# Buck_Converter_and_LDO.net
KiCad netlist of a schematic drawn in Altium Designer
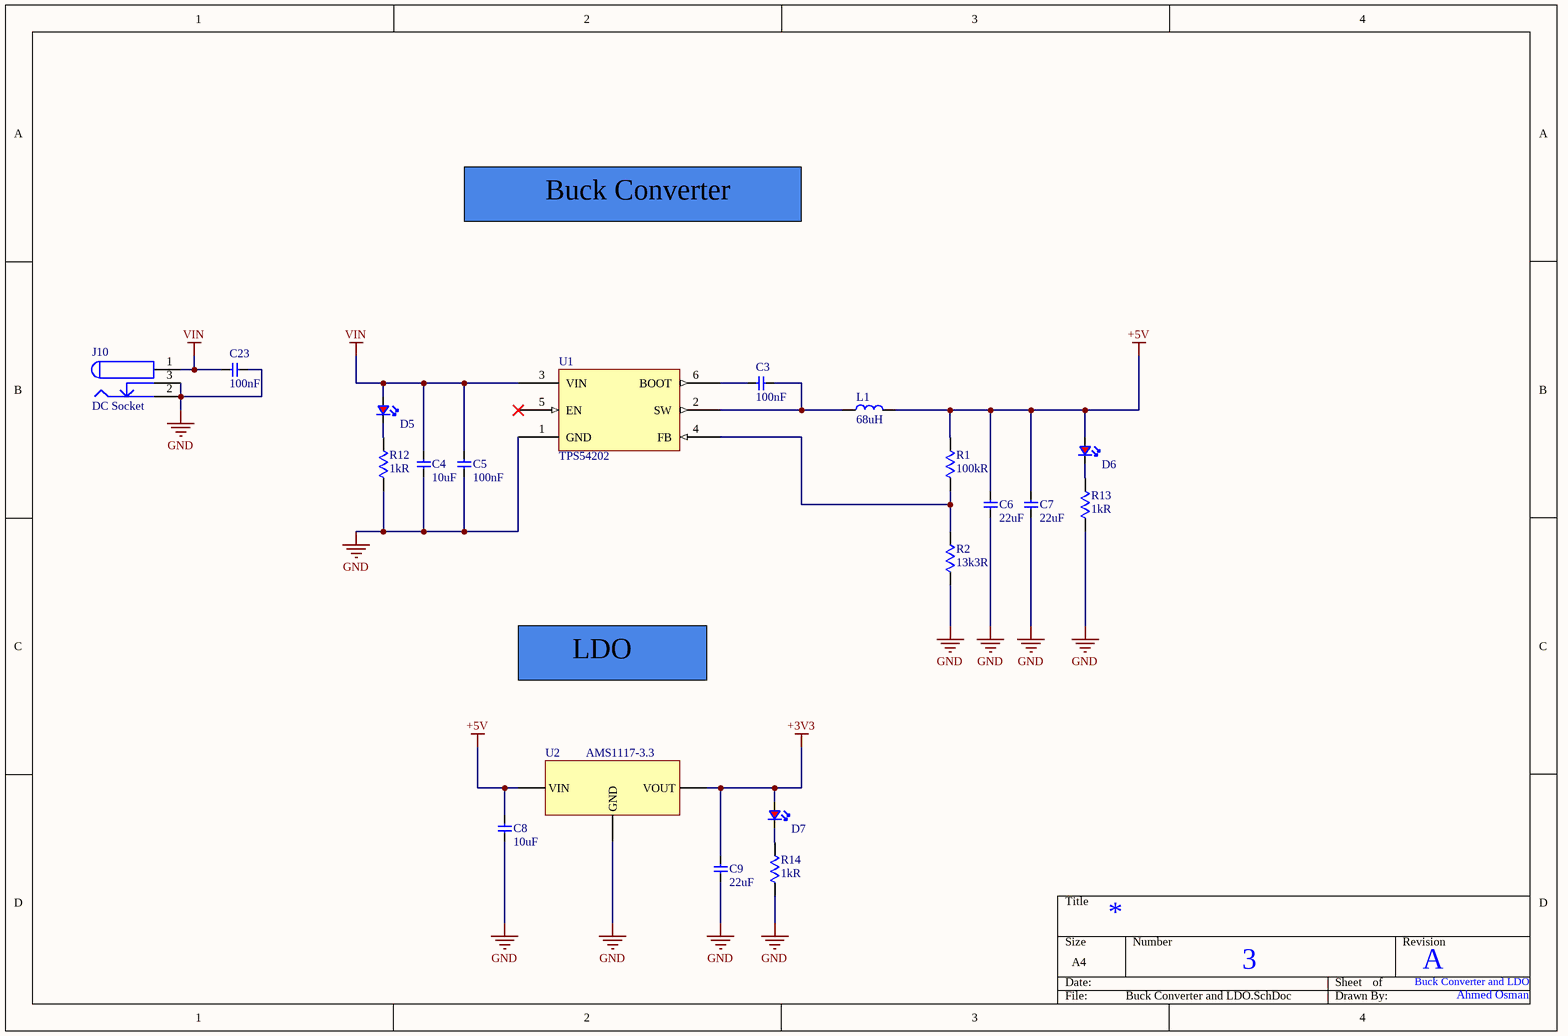
[diagram p0: Buck Converter and LDO.SchDoc]

(export (version "E")
  (design (tool "Eeschema 10.0.6"))
  (components
    (comp (ref "C3")
      (value "100nF")
      (footprint "CAP 0603")
      (description "0.1 µF ±10% 50V Ceramic Capacitor X7R 0603 (1608 Metric)")
      (fields (field (name "TOLERANCE") "10%") (field (name "VOLTAGE") "50V"))
      (libsource (lib "Temperature project symbols") (part "CAP  0603 100nF 10% 50 V"))
    )
    (comp (ref "C4")
      (value "10uF")
      (footprint "CAP 0603")
      (description "10 µF ±20% 35V Ceramic Capacitor X5R 0603 (1608 Metric)")
      (fields
        (field (name "MANUFACTURER") "Murata")
        (field (name "MANUFACTURER PART NUMBER") "GRM188R6YA106MA73D")
      )
      (libsource (lib "Temperature project symbols") (part "CAP 0603 10 µF ±20% 35V _1"))
    )
    (comp (ref "C5")
      (value "100nF")
      (footprint "CAP 0603")
      (description "0.1 µF ±10% 50V Ceramic Capacitor X7R 0603 (1608 Metric)")
      (fields (field (name "TOLERANCE") "10%") (field (name "VOLTAGE") "50V"))
      (libsource (lib "Temperature project symbols") (part "CAP  0603 100nF 10% 50 V"))
    )
    (comp (ref "C6")
      (value "22uF")
      (footprint "CAP 0603")
      (description "10V 22uF X5R ±20% 0603 Multilayer Ceramic Capacitors MLCC - SMD/SMT ROHS")
      (libsource (lib "Temperature project symbols") (part "CAP  0603 22 µF ±20% 10V"))
    )
    (comp (ref "C7")
      (value "22uF")
      (footprint "CAP 0603")
      (description "10V 22uF X5R ±20% 0603 Multilayer Ceramic Capacitors MLCC - SMD/SMT ROHS")
      (libsource (lib "Temperature project symbols") (part "CAP  0603 22 µF ±20% 10V"))
    )
    (comp (ref "C8")
      (value "10uF")
      (footprint "CAP 0603")
      (description "10 µF ±20% 35V Ceramic Capacitor X5R 0603 (1608 Metric)")
      (fields
        (field (name "MANUFACTURER") "Murata")
        (field (name "MANUFACTURER PART NUMBER") "GRM188R6YA106MA73D")
      )
      (libsource (lib "Temperature project symbols") (part "CAP 0603 10 µF ±20% 35V"))
    )
    (comp (ref "C9")
      (value "22uF")
      (footprint "CAP 0603")
      (description "10V 22uF X5R ±20% 0603 Multilayer Ceramic Capacitors MLCC - SMD/SMT ROHS")
      (libsource (lib "Temperature project symbols") (part "CAP  0603 22 µF ±20% 10V"))
    )
    (comp (ref "C23")
      (value "100nF")
      (footprint "CAP 0603")
      (description "0.1 µF ±10% 50V Ceramic Capacitor X7R 0603 (1608 Metric)")
      (fields (field (name "TOLERANCE") "10%") (field (name "VOLTAGE") "50V"))
      (libsource (lib "Temperature project symbols") (part "CAP  0603 100 nF 10% 50 V"))
    )
    (comp (ref "D5")
      (value "LED RED")
      (footprint "LED RED")
      (description "Red 625nm LED Indication - Discrete 2V 0603 (1608 Metric)")
      (libsource (lib "Temperature project symbols") (part "LED RED"))
    )
    (comp (ref "D6")
      (value "LED RED")
      (footprint "LED RED")
      (description "Red 625nm LED Indication - Discrete 2V 0603 (1608 Metric)")
      (libsource (lib "Temperature project symbols") (part "LED RED"))
    )
    (comp (ref "D7")
      (value "LED RED")
      (footprint "LED RED")
      (description "Red 625nm LED Indication - Discrete 2V 0603 (1608 Metric)")
      (libsource (lib "Temperature project symbols") (part "LED RED"))
    )
    (comp (ref "J10")
      (value "DC Socket")
      (footprint "DC Socket")
      (description "Bend-in DC Power Receptacle -20℃~+70℃ 2.5mm 6.3mm 3A 30V Plugin DC Power Connectors ROHS")
      (libsource (lib "Temperature project symbols") (part "DC Socket"))
    )
    (comp (ref "L1")
      (value "68uH")
      (footprint "Inductor SMD,12.3x12.3mm")
      (description "2.1A 68uH ±20% 140mΩ SMD,12.3x12.3mm Inductors (SMD) ROHS")
      (fields (field (name "MANUFACTURE PART NUMBER") "CYH127-68UH"))
      (libsource (lib "Temperature project symbols") (part "IND  12.3x12.3mm 68uH ±20% 140mΩ_1"))
    )
    (comp (ref "R1")
      (value "100kR")
      (footprint "RES 0603")
      (description "100 kOhms ±0.1% 0.1W, 1/10W Chip Resistor 0603 (1608 Metric) Thin Film")
      (fields (field (name "TOLERANCE") "0.1%"))
      (libsource (lib "Temperature project symbols") (part "RES  0603 100KR 0.1% 1/10W"))
    )
    (comp (ref "R2")
      (value "13k3R")
      (footprint "RES 0603")
      (description "13.3 kOhms ±1% 0.1W, 1/10W Chip Resistor 0603 (1608 Metric) Thin Film")
      (fields (field (name "MANUFACTURER") "Yageo") (field (name "TOLERANCE") "1%"))
      (libsource (lib "Temperature project symbols") (part "RES  0603 13.3kR ±1% 0.1W"))
    )
    (comp (ref "R12")
      (value "1kR")
      (footprint "RES 0603")
      (description "1 kOhms ±1% 0.1W, 1/10W Chip Resistor 0603 (1608 Metric) Moisture Resistant Thick Film")
      (fields (field (name "MANUFACTURER") "Yageo") (field (name "TOLERANCE") "1%"))
      (libsource (lib "Temperature project symbols") (part "RES  0603 1kR ±1% 0.1W"))
    )
    (comp (ref "R13")
      (value "1kR")
      (footprint "RES 0603")
      (description "1 kOhms ±1% 0.1W, 1/10W Chip Resistor 0603 (1608 Metric) Moisture Resistant Thick Film")
      (fields (field (name "MANUFACTURER") "Yageo") (field (name "TOLERANCE") "1%"))
      (libsource (lib "Temperature project symbols") (part "RES  0603 1kR ±1% 0.1W"))
    )
    (comp (ref "R14")
      (value "1kR")
      (footprint "RES 0603")
      (description "1 kOhms ±1% 0.1W, 1/10W Chip Resistor 0603 (1608 Metric) Moisture Resistant Thick Film")
      (fields (field (name "MANUFACTURER") "Yageo") (field (name "TOLERANCE") "1%"))
      (libsource (lib "Temperature project symbols") (part "RES  0603 1kR ±1% 0.1W"))
    )
    (comp (ref "U1")
      (value "TPS54202")
      (footprint "SOT-23-6")
      (description "Buck Switching Regulator IC Positive Adjustable 0.596V 1 Output 2A SOT-23-6 Thin, TSOT-23-6")
      (libsource (lib "Temperature project symbols") (part "TPS54202"))
    )
    (comp (ref "U2")
      (value "AMS1117-3.3")
      (footprint "SOT-223-3L")
      (description "Linear Voltage Regulator IC Positive Fixed 1 Output 1A SOT-223-3L")
      (libsource (lib "Temperature project symbols") (part "AMS1117-3.3"))
    )
  )
  (nets
    (net (code "1") (name "+3V3") (class "Default")
      (node (ref "C9") (pin "2") (pintype "passive"))
      (node (ref "D7") (pin "2") (pinfunction "2_2") (pintype "passive"))
      (node (ref "U2") (pin "2") (pinfunction "VOUT_2") (pintype "passive"))
    )
    (net (code "2") (name "+5V") (class "Default")
      (node (ref "C6") (pin "2") (pintype "passive"))
      (node (ref "C7") (pin "2") (pintype "passive"))
      (node (ref "C8") (pin "2") (pintype "passive"))
      (node (ref "D6") (pin "2") (pinfunction "2_2") (pintype "passive"))
      (node (ref "L1") (pin "2") (pinfunction "2_2") (pintype "passive"))
      (node (ref "R1") (pin "2") (pinfunction "2_2") (pintype "passive"))
      (node (ref "U2") (pin "3") (pinfunction "VIN_3") (pintype "passive"))
    )
    (net (code "3") (name "GND") (class "Default")
      (node (ref "C23") (pin "2") (pintype "passive"))
      (node (ref "C4") (pin "2") (pintype "passive"))
      (node (ref "C5") (pin "1") (pintype "passive"))
      (node (ref "C6") (pin "1") (pintype "passive"))
      (node (ref "C7") (pin "1") (pintype "passive"))
      (node (ref "C8") (pin "1") (pintype "passive"))
      (node (ref "C9") (pin "1") (pintype "passive"))
      (node (ref "J10") (pin "2") (pinfunction "GND_2") (pintype "passive"))
      (node (ref "J10") (pin "3") (pinfunction "GND_3") (pintype "passive"))
      (node (ref "R12") (pin "1") (pinfunction "1_1") (pintype "passive"))
      (node (ref "R13") (pin "1") (pinfunction "1_1") (pintype "passive"))
      (node (ref "R14") (pin "1") (pinfunction "1_1") (pintype "passive"))
      (node (ref "R2") (pin "2") (pinfunction "2_2") (pintype "passive"))
      (node (ref "U1") (pin "1") (pinfunction "GND_1") (pintype "power_in"))
      (node (ref "U2") (pin "1") (pinfunction "GND_1") (pintype "passive"))
    )
    (net (code "4") (name "Net-(D5-Pad1)") (class "Default")
      (node (ref "D5") (pin "1") (pinfunction "1_1") (pintype "passive"))
      (node (ref "R12") (pin "2") (pinfunction "2_2") (pintype "passive"))
    )
    (net (code "5") (name "Net-(D6-Pad1)") (class "Default")
      (node (ref "D6") (pin "1") (pinfunction "1_1") (pintype "passive"))
      (node (ref "R13") (pin "2") (pinfunction "2_2") (pintype "passive"))
    )
    (net (code "6") (name "Net-(D7-Pad1)") (class "Default")
      (node (ref "D7") (pin "1") (pinfunction "1_1") (pintype "passive"))
      (node (ref "R14") (pin "2") (pinfunction "2_2") (pintype "passive"))
    )
    (net (code "7") (name "Net-(U1-BOOT)") (class "Default")
      (node (ref "C3") (pin "1") (pintype "passive"))
      (node (ref "U1") (pin "6") (pinfunction "BOOT_6") (pintype "output"))
    )
    (net (code "8") (name "Net-(U1-FB)") (class "Default")
      (node (ref "R1") (pin "1") (pinfunction "1_1") (pintype "passive"))
      (node (ref "R2") (pin "1") (pinfunction "1_1") (pintype "passive"))
      (node (ref "U1") (pin "4") (pinfunction "FB_4") (pintype "input"))
    )
    (net (code "9") (name "Net-(U1-SW)") (class "Default")
      (node (ref "C3") (pin "2") (pintype "passive"))
      (node (ref "L1") (pin "1") (pinfunction "2_1") (pintype "passive"))
      (node (ref "U1") (pin "2") (pinfunction "SW_2") (pintype "output"))
    )
    (net (code "10") (name "VIN") (class "Default")
      (node (ref "C23") (pin "1") (pintype "passive"))
      (node (ref "C4") (pin "1") (pintype "passive"))
      (node (ref "C5") (pin "2") (pintype "passive"))
      (node (ref "D5") (pin "2") (pinfunction "2_2") (pintype "passive"))
      (node (ref "J10") (pin "1") (pinfunction "VIN_1") (pintype "passive"))
      (node (ref "U1") (pin "3") (pinfunction "VIN_3") (pintype "power_in"))
    )
    (net (code "11") (name "unconnected-(U1-EN-Pad5)") (class "Default")
      (node (ref "U1") (pin "5") (pinfunction "EN_5") (pintype "input+no_connect"))
    )
  )
)
